# Moist_Led.net
KiCad netlist of a schematic drawn in EAGLE
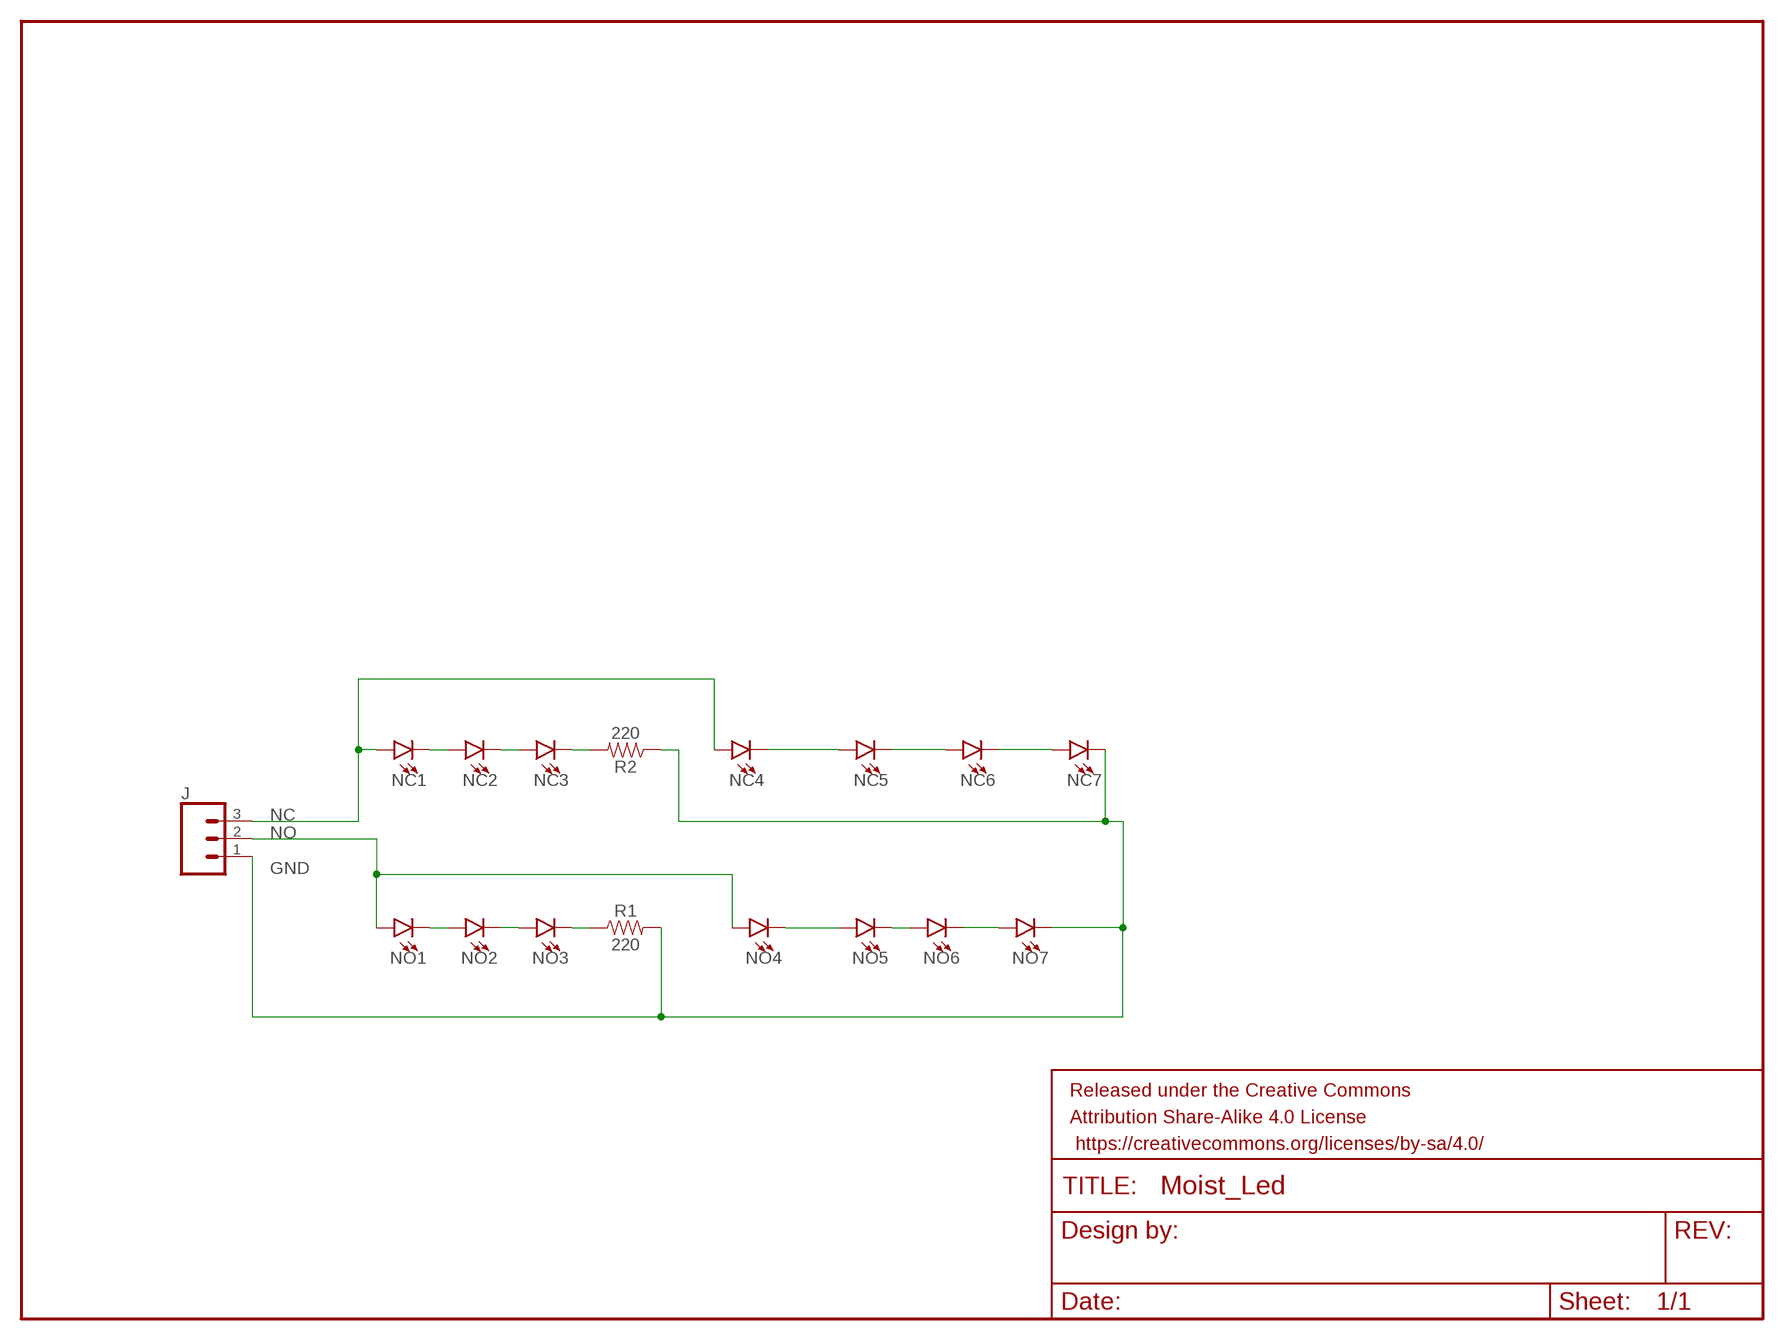
[diagram p0: schematic, sheet 1]

(export (version "E")
  (design (tool "Eeschema 10.0.6"))
  (components
    (comp (ref "FRAME1")
      (value "FRAME-LETTER")
      (footprint "eagle-import:CREATIVE_COMMONS")
      (libsource (lib "eagle-import") (part "FRAME-LETTER"))
    )
    (comp (ref "J")
      (value "CONN_03")
      (footprint "eagle-import:1X03")
      (libsource (lib "eagle-import") (part "CONN_03"))
    )
    (comp (ref "NC1")
      (value "LED5MM")
      (footprint "eagle-import:LED_5MM")
      (libsource (lib "eagle-import") (part "LED5MM"))
    )
    (comp (ref "NC2")
      (value "LED5MM")
      (footprint "eagle-import:LED_5MM")
      (libsource (lib "eagle-import") (part "LED5MM"))
    )
    (comp (ref "NC3")
      (value "LED5MM")
      (footprint "eagle-import:LED_5MM")
      (libsource (lib "eagle-import") (part "LED5MM"))
    )
    (comp (ref "NC4")
      (value "LED5MM")
      (footprint "eagle-import:LED_5MM")
      (libsource (lib "eagle-import") (part "LED5MM"))
    )
    (comp (ref "NC5")
      (value "LED5MM")
      (footprint "eagle-import:LED_5MM")
      (libsource (lib "eagle-import") (part "LED5MM"))
    )
    (comp (ref "NC6")
      (value "LED5MM")
      (footprint "eagle-import:LED_5MM")
      (libsource (lib "eagle-import") (part "LED5MM"))
    )
    (comp (ref "NC7")
      (value "LED5MM")
      (footprint "eagle-import:LED_5MM")
      (libsource (lib "eagle-import") (part "LED5MM"))
    )
    (comp (ref "NO1")
      (value "LED5MM")
      (footprint "eagle-import:LED_5MM")
      (libsource (lib "eagle-import") (part "LED5MM"))
    )
    (comp (ref "NO2")
      (value "LED5MM")
      (footprint "eagle-import:LED_5MM")
      (libsource (lib "eagle-import") (part "LED5MM"))
    )
    (comp (ref "NO3")
      (value "LED5MM")
      (footprint "eagle-import:LED_5MM")
      (libsource (lib "eagle-import") (part "LED5MM"))
    )
    (comp (ref "NO4")
      (value "LED5MM")
      (footprint "eagle-import:LED_5MM")
      (libsource (lib "eagle-import") (part "LED5MM"))
    )
    (comp (ref "NO5")
      (value "LED5MM")
      (footprint "eagle-import:LED_5MM")
      (libsource (lib "eagle-import") (part "LED5MM"))
    )
    (comp (ref "NO6")
      (value "LED5MM")
      (footprint "eagle-import:LED_5MM")
      (libsource (lib "eagle-import") (part "LED5MM"))
    )
    (comp (ref "NO7")
      (value "LED5MM")
      (footprint "eagle-import:LED_5MM")
      (libsource (lib "eagle-import") (part "LED5MM"))
    )
    (comp (ref "R1")
      (value "220")
      (footprint "eagle-import:AXIAL-0.3")
      (libsource (lib "eagle-import") (part "10OHM-HORIZ-1/4W-1%"))
    )
    (comp (ref "R2")
      (value "220")
      (footprint "eagle-import:AXIAL-0.3")
      (libsource (lib "eagle-import") (part "10OHM-HORIZ-1/4W-1%"))
    )
  )
  (nets
    (net (code "1") (name "/GND") (class "Default")
      (node (ref "J") (pin "1") (pinfunction "1_1") (pintype "passive"))
      (node (ref "NC7") (pin "K") (pinfunction "C_K") (pintype "passive"))
      (node (ref "NO7") (pin "K") (pinfunction "C_K") (pintype "passive"))
      (node (ref "R1") (pin "P$2") (pinfunction "2_P$2") (pintype "passive"))
      (node (ref "R2") (pin "P$1") (pinfunction "1_P$1") (pintype "passive"))
    )
    (net (code "2") (name "/NC") (class "Default")
      (node (ref "J") (pin "3") (pinfunction "3_3") (pintype "passive"))
      (node (ref "NC1") (pin "A") (pinfunction "A_A") (pintype "passive"))
      (node (ref "NC4") (pin "A") (pinfunction "A_A") (pintype "passive"))
    )
    (net (code "3") (name "/NO") (class "Default")
      (node (ref "J") (pin "2") (pinfunction "2_2") (pintype "passive"))
      (node (ref "NO1") (pin "A") (pinfunction "A_A") (pintype "passive"))
      (node (ref "NO4") (pin "A") (pinfunction "A_A") (pintype "passive"))
    )
    (net (code "4") (name "Net-(NC1-C)") (class "Default")
      (node (ref "NC1") (pin "K") (pinfunction "C_K") (pintype "passive"))
      (node (ref "NC2") (pin "A") (pinfunction "A_A") (pintype "passive"))
    )
    (net (code "5") (name "Net-(NC2-C)") (class "Default")
      (node (ref "NC2") (pin "K") (pinfunction "C_K") (pintype "passive"))
      (node (ref "NC3") (pin "A") (pinfunction "A_A") (pintype "passive"))
    )
    (net (code "6") (name "Net-(NC3-C)") (class "Default")
      (node (ref "NC3") (pin "K") (pinfunction "C_K") (pintype "passive"))
      (node (ref "R2") (pin "P$2") (pinfunction "2_P$2") (pintype "passive"))
    )
    (net (code "7") (name "Net-(NC4-C)") (class "Default")
      (node (ref "NC4") (pin "K") (pinfunction "C_K") (pintype "passive"))
      (node (ref "NC5") (pin "A") (pinfunction "A_A") (pintype "passive"))
    )
    (net (code "8") (name "Net-(NC5-C)") (class "Default")
      (node (ref "NC5") (pin "K") (pinfunction "C_K") (pintype "passive"))
      (node (ref "NC6") (pin "A") (pinfunction "A_A") (pintype "passive"))
    )
    (net (code "9") (name "Net-(NC6-C)") (class "Default")
      (node (ref "NC6") (pin "K") (pinfunction "C_K") (pintype "passive"))
      (node (ref "NC7") (pin "A") (pinfunction "A_A") (pintype "passive"))
    )
    (net (code "10") (name "Net-(NO1-C)") (class "Default")
      (node (ref "NO1") (pin "K") (pinfunction "C_K") (pintype "passive"))
      (node (ref "NO2") (pin "A") (pinfunction "A_A") (pintype "passive"))
    )
    (net (code "11") (name "Net-(NO2-C)") (class "Default")
      (node (ref "NO2") (pin "K") (pinfunction "C_K") (pintype "passive"))
      (node (ref "NO3") (pin "A") (pinfunction "A_A") (pintype "passive"))
    )
    (net (code "12") (name "Net-(NO3-C)") (class "Default")
      (node (ref "NO3") (pin "K") (pinfunction "C_K") (pintype "passive"))
      (node (ref "R1") (pin "P$1") (pinfunction "1_P$1") (pintype "passive"))
    )
    (net (code "13") (name "Net-(NO4-C)") (class "Default")
      (node (ref "NO4") (pin "K") (pinfunction "C_K") (pintype "passive"))
      (node (ref "NO5") (pin "A") (pinfunction "A_A") (pintype "passive"))
    )
    (net (code "14") (name "Net-(NO5-C)") (class "Default")
      (node (ref "NO5") (pin "K") (pinfunction "C_K") (pintype "passive"))
      (node (ref "NO6") (pin "A") (pinfunction "A_A") (pintype "passive"))
    )
    (net (code "15") (name "Net-(NO6-C)") (class "Default")
      (node (ref "NO6") (pin "K") (pinfunction "C_K") (pintype "passive"))
      (node (ref "NO7") (pin "A") (pinfunction "A_A") (pintype "passive"))
    )
  )
)
